# tracker4.net
KiCad netlist of a schematic drawn in EAGLE
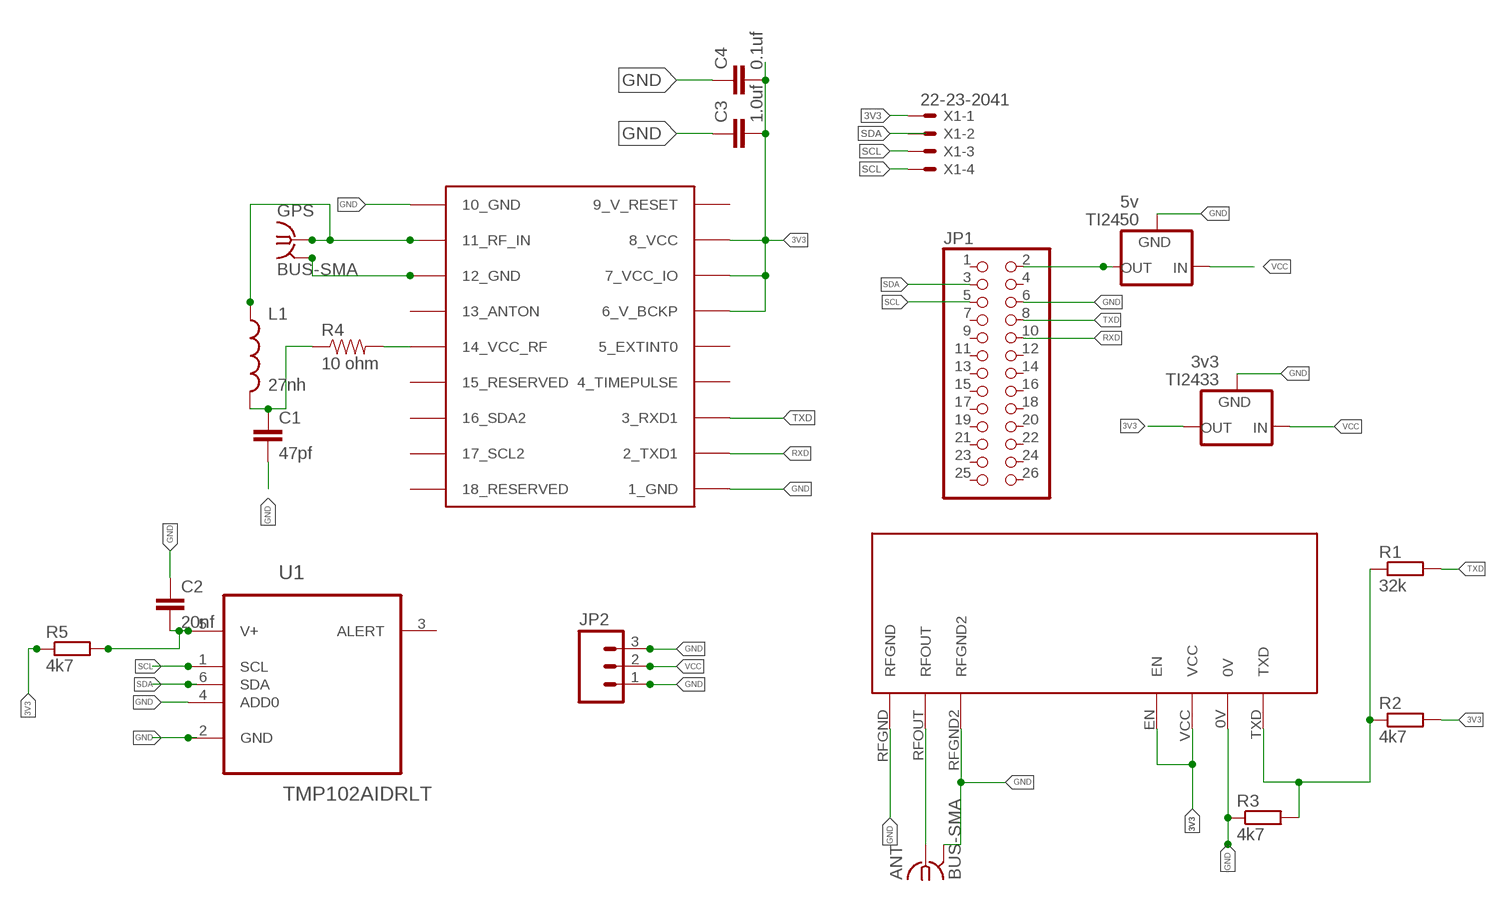
[diagram p0: schematic, sheet 1]

(export (version "E")
  (design (tool "Eeschema 10.0.6"))
  (components
    (comp (ref "ANT")
      (value "BUS-SMA")
      (footprint "eagle-import:BUS-SMA")
      (libsource (lib "eagle-import") (part "BUS-SMA"))
    )
    (comp (ref "C1")
      (value "47pf")
      (footprint "eagle-import:0603-CAP")
      (libsource (lib "eagle-import") (part "CAP0603-CAP"))
    )
    (comp (ref "C2")
      (value "20nf")
      (footprint "eagle-import:C0603")
      (libsource (lib "eagle-import") (part "C-EUC0603"))
    )
    (comp (ref "C3")
      (value "1.0uf")
      (footprint "eagle-import:C0603")
      (libsource (lib "eagle-import") (part "C-EUC0603"))
    )
    (comp (ref "C4")
      (value "0.1uf")
      (footprint "eagle-import:C0603")
      (libsource (lib "eagle-import") (part "C-EUC0603"))
    )
    (comp (ref "GPS")
      (value "BUS-SMA")
      (footprint "eagle-import:BUS-SMA")
      (libsource (lib "eagle-import") (part "BUS-SMA"))
    )
    (comp (ref "JP1")
      (value "PINHD-2X13")
      (footprint "eagle-import:2X13")
      (libsource (lib "eagle-import") (part "PINHD-2X13"))
    )
    (comp (ref "JP2")
      (value "M03PTH")
      (footprint "eagle-import:1X03")
      (libsource (lib "eagle-import") (part "M03PTH"))
    )
    (comp (ref "L1")
      (value "27nh")
      (footprint "eagle-import:0603")
      (libsource (lib "eagle-import") (part "INDUCTOR0603"))
    )
    (comp (ref "R1")
      (value "32k")
      (footprint "eagle-import:R0603")
      (libsource (lib "eagle-import") (part "R-EU_R0603"))
    )
    (comp (ref "R2")
      (value "4k7")
      (footprint "eagle-import:R0603")
      (libsource (lib "eagle-import") (part "R-EU_R0603"))
    )
    (comp (ref "R3")
      (value "4k7")
      (footprint "eagle-import:R0603")
      (libsource (lib "eagle-import") (part "R-EU_R0603"))
    )
    (comp (ref "R4")
      (value "10 ohm")
      (footprint "eagle-import:0603-RES")
      (libsource (lib "eagle-import") (part "RESISTOR0603"))
    )
    (comp (ref "R5")
      (value "4k7")
      (footprint "eagle-import:R0603")
      (libsource (lib "eagle-import") (part "R-EU_R0603"))
    )
    (comp (ref "TI2433")
      (value "3v3")
      (footprint "eagle-import:TO-220-ALT")
      (libsource (lib "eagle-import") (part "V_REG_78XX-TO-220"))
    )
    (comp (ref "TI2450")
      (value "5v")
      (footprint "eagle-import:TO-220-ALT")
      (libsource (lib "eagle-import") (part "V_REG_78XX-TO-220"))
    )
    (comp (ref "U$1")
      (value "NTX2")
      (footprint "eagle-import:NTX2")
      (libsource (lib "eagle-import") (part "NTX2"))
    )
    (comp (ref "U$2")
      (value "UBLOX_MAX")
      (footprint "eagle-import:UBLOX_MAX")
      (libsource (lib "eagle-import") (part "UBLOX_MAX"))
    )
    (comp (ref "U1")
      (value "TMP102AIDRLT")
      (footprint "eagle-import:SOT50P160X60-6N")
      (libsource (lib "eagle-import") (part "TMP102AIDRLT"))
    )
    (comp (ref "X1")
      (value "22-23-2041")
      (footprint "eagle-import:22-23-2041")
      (fields (field (name "MF") "MOLEX"))
      (libsource (lib "eagle-import") (part "22-23-2041"))
    )
  )
  (nets
    (net (code "1") (name "/9_V_RESET") (class "Default")
      (node (ref "U$2") (pin "9_V_RESET") (pinfunction "9_V_RESET_9_V_RESET") (pintype "power_in"))
    )
    (net (code "2") (name "3V3") (class "Default")
      (node (ref "C2") (pin "2") (pinfunction "2_2") (pintype "passive"))
      (node (ref "C3") (pin "2") (pinfunction "2_2") (pintype "passive"))
      (node (ref "C4") (pin "2") (pinfunction "2_2") (pintype "passive"))
      (node (ref "R2") (pin "2") (pinfunction "2_2") (pintype "passive"))
      (node (ref "R5") (pin "1") (pinfunction "1_1") (pintype "passive"))
      (node (ref "R5") (pin "2") (pinfunction "2_2") (pintype "passive"))
      (node (ref "TI2433") (pin "OUT") (pinfunction "OUT_OUT") (pintype "output"))
      (node (ref "U$1") (pin "EN") (pinfunction "EN_EN") (pintype "bidirectional"))
      (node (ref "U$1") (pin "VCC") (pinfunction "VCC_VCC") (pintype "bidirectional"))
      (node (ref "U$2") (pin "6_V_BCKP") (pinfunction "6_V_BCKP_6_V_BCKP") (pintype "bidirectional"))
      (node (ref "U$2") (pin "7_VCC_IO") (pinfunction "7_VCC_IO_7_VCC_IO") (pintype "power_in"))
      (node (ref "U$2") (pin "8_VCC") (pinfunction "8_VCC_8_VCC") (pintype "power_in"))
      (node (ref "U1") (pin "5") (pinfunction "V+_5") (pintype "power_in"))
      (node (ref "X1") (pin "1") (pinfunction "S_1") (pintype "passive"))
    )
    (net (code "3") (name "GND") (class "Default")
      (node (ref "ANT") (pin "2") (pinfunction "GND_2") (pintype "power_in"))
      (node (ref "ANT") (pin "3") (pinfunction "GND_3") (pintype "power_in"))
      (node (ref "ANT") (pin "4") (pinfunction "GND_4") (pintype "power_in"))
      (node (ref "ANT") (pin "5") (pinfunction "GND_5") (pintype "power_in"))
      (node (ref "C1") (pin "2") (pinfunction "2_2") (pintype "passive"))
      (node (ref "C2") (pin "1") (pinfunction "1_1") (pintype "passive"))
      (node (ref "C3") (pin "1") (pinfunction "1_1") (pintype "passive"))
      (node (ref "C4") (pin "1") (pinfunction "1_1") (pintype "passive"))
      (node (ref "GPS") (pin "2") (pinfunction "GND_2") (pintype "power_in"))
      (node (ref "GPS") (pin "3") (pinfunction "GND_3") (pintype "power_in"))
      (node (ref "GPS") (pin "4") (pinfunction "GND_4") (pintype "power_in"))
      (node (ref "GPS") (pin "5") (pinfunction "GND_5") (pintype "power_in"))
      (node (ref "JP1") (pin "6") (pinfunction "6_6") (pintype "passive"))
      (node (ref "JP2") (pin "1") (pinfunction "1_1") (pintype "passive"))
      (node (ref "JP2") (pin "3") (pinfunction "3_3") (pintype "passive"))
      (node (ref "R3") (pin "1") (pinfunction "1_1") (pintype "passive"))
      (node (ref "TI2433") (pin "GND") (pinfunction "GND_GND") (pintype "input"))
      (node (ref "TI2450") (pin "GND") (pinfunction "GND_GND") (pintype "input"))
      (node (ref "U$1") (pin "0V") (pinfunction "0V_0V") (pintype "bidirectional"))
      (node (ref "U$1") (pin "RFGND") (pinfunction "RFGND_RFGND") (pintype "bidirectional"))
      (node (ref "U$1") (pin "RFGND2") (pinfunction "RFGND2_RFGND2") (pintype "bidirectional"))
      (node (ref "U$2") (pin "10_GND") (pinfunction "10_GND_10_GND") (pintype "power_in"))
      (node (ref "U$2") (pin "12_GND") (pinfunction "12_GND_12_GND") (pintype "power_in"))
      (node (ref "U$2") (pin "1_GND") (pinfunction "1_GND_1_GND") (pintype "power_in"))
      (node (ref "U1") (pin "2") (pinfunction "GND_2") (pintype "passive"))
      (node (ref "U1") (pin "4") (pinfunction "ADD0_4") (pintype "input"))
      (node (ref "X1") (pin "4") (pinfunction "S_4") (pintype "passive"))
    )
    (net (code "4") (name "Net-(ANT-Pad1)") (class "Default")
      (node (ref "ANT") (pin "1") (pinfunction "1_1") (pintype "passive"))
      (node (ref "U$1") (pin "RFOUT") (pinfunction "RFOUT_RFOUT") (pintype "bidirectional"))
    )
    (net (code "5") (name "Net-(C1-Pad1)") (class "Default")
      (node (ref "C1") (pin "1") (pinfunction "1_1") (pintype "passive"))
      (node (ref "L1") (pin "2") (pinfunction "2_2") (pintype "passive"))
      (node (ref "R4") (pin "1") (pinfunction "1_1") (pintype "passive"))
    )
    (net (code "6") (name "Net-(GPS-Pad1)") (class "Default")
      (node (ref "GPS") (pin "1") (pinfunction "1_1") (pintype "passive"))
      (node (ref "L1") (pin "1") (pinfunction "1_1") (pintype "passive"))
      (node (ref "U$2") (pin "11_RF_IN") (pinfunction "11_RF_IN_11_RF_IN") (pintype "bidirectional"))
    )
    (net (code "7") (name "Net-(JP1-Pad2)") (class "Default")
      (node (ref "JP1") (pin "2") (pinfunction "2_2") (pintype "passive"))
      (node (ref "TI2450") (pin "OUT") (pinfunction "OUT_OUT") (pintype "output"))
    )
    (net (code "8") (name "Net-(R1-Pad1)") (class "Default")
      (node (ref "R1") (pin "1") (pinfunction "1_1") (pintype "passive"))
      (node (ref "R2") (pin "1") (pinfunction "1_1") (pintype "passive"))
      (node (ref "R3") (pin "2") (pinfunction "2_2") (pintype "passive"))
      (node (ref "U$1") (pin "TXD") (pinfunction "TXD_TXD") (pintype "bidirectional"))
    )
    (net (code "9") (name "Net-(R4-Pad2)") (class "Default")
      (node (ref "R4") (pin "2") (pinfunction "2_2") (pintype "passive"))
      (node (ref "U$2") (pin "14_VCC_RF") (pinfunction "14_VCC_RF_14_VCC_RF") (pintype "bidirectional"))
    )
    (net (code "10") (name "RXD") (class "Default")
      (node (ref "JP1") (pin "10") (pinfunction "10_10") (pintype "passive"))
      (node (ref "U$2") (pin "2_TXD1") (pinfunction "2_TXD1_2_TXD1") (pintype "bidirectional"))
    )
    (net (code "11") (name "SCL") (class "Default")
      (node (ref "JP1") (pin "5") (pinfunction "5_5") (pintype "passive"))
      (node (ref "U1") (pin "1") (pinfunction "SCL_1") (pintype "bidirectional"))
      (node (ref "X1") (pin "3") (pinfunction "S_3") (pintype "passive"))
    )
    (net (code "12") (name "SDA") (class "Default")
      (node (ref "JP1") (pin "3") (pinfunction "3_3") (pintype "passive"))
      (node (ref "U1") (pin "6") (pinfunction "SDA_6") (pintype "bidirectional"))
      (node (ref "X1") (pin "2") (pinfunction "S_2") (pintype "passive"))
    )
    (net (code "13") (name "TXD") (class "Default")
      (node (ref "JP1") (pin "8") (pinfunction "8_8") (pintype "passive"))
      (node (ref "R1") (pin "2") (pinfunction "2_2") (pintype "passive"))
      (node (ref "U$2") (pin "3_RXD1") (pinfunction "3_RXD1_3_RXD1") (pintype "bidirectional"))
    )
    (net (code "14") (name "VCC") (class "Default")
      (node (ref "JP2") (pin "2") (pinfunction "2_2") (pintype "passive"))
      (node (ref "TI2433") (pin "IN") (pinfunction "IN_IN") (pintype "input"))
      (node (ref "TI2450") (pin "IN") (pinfunction "IN_IN") (pintype "input"))
    )
    (net (code "15") (name "unconnected-(JP1-Pad1)") (class "Default")
      (node (ref "JP1") (pin "1") (pinfunction "1_1") (pintype "passive"))
    )
    (net (code "16") (name "unconnected-(JP1-Pad4)") (class "Default")
      (node (ref "JP1") (pin "4") (pinfunction "4_4") (pintype "passive"))
    )
    (net (code "17") (name "unconnected-(JP1-Pad7)") (class "Default")
      (node (ref "JP1") (pin "7") (pinfunction "7_7") (pintype "passive"))
    )
    (net (code "18") (name "unconnected-(JP1-Pad9)") (class "Default")
      (node (ref "JP1") (pin "9") (pinfunction "9_9") (pintype "passive"))
    )
    (net (code "19") (name "unconnected-(JP1-Pad11)") (class "Default")
      (node (ref "JP1") (pin "11") (pinfunction "11_11") (pintype "passive"))
    )
    (net (code "20") (name "unconnected-(JP1-Pad12)") (class "Default")
      (node (ref "JP1") (pin "12") (pinfunction "12_12") (pintype "passive"))
    )
    (net (code "21") (name "unconnected-(JP1-Pad13)") (class "Default")
      (node (ref "JP1") (pin "13") (pinfunction "13_13") (pintype "passive"))
    )
    (net (code "22") (name "unconnected-(JP1-Pad14)") (class "Default")
      (node (ref "JP1") (pin "14") (pinfunction "14_14") (pintype "passive"))
    )
    (net (code "23") (name "unconnected-(JP1-Pad15)") (class "Default")
      (node (ref "JP1") (pin "15") (pinfunction "15_15") (pintype "passive"))
    )
    (net (code "24") (name "unconnected-(JP1-Pad16)") (class "Default")
      (node (ref "JP1") (pin "16") (pinfunction "16_16") (pintype "passive"))
    )
    (net (code "25") (name "unconnected-(JP1-Pad17)") (class "Default")
      (node (ref "JP1") (pin "17") (pinfunction "17_17") (pintype "passive"))
    )
    (net (code "26") (name "unconnected-(JP1-Pad18)") (class "Default")
      (node (ref "JP1") (pin "18") (pinfunction "18_18") (pintype "passive"))
    )
    (net (code "27") (name "unconnected-(JP1-Pad19)") (class "Default")
      (node (ref "JP1") (pin "19") (pinfunction "19_19") (pintype "passive"))
    )
    (net (code "28") (name "unconnected-(JP1-Pad20)") (class "Default")
      (node (ref "JP1") (pin "20") (pinfunction "20_20") (pintype "passive"))
    )
    (net (code "29") (name "unconnected-(JP1-Pad21)") (class "Default")
      (node (ref "JP1") (pin "21") (pinfunction "21_21") (pintype "passive"))
    )
    (net (code "30") (name "unconnected-(JP1-Pad22)") (class "Default")
      (node (ref "JP1") (pin "22") (pinfunction "22_22") (pintype "passive"))
    )
    (net (code "31") (name "unconnected-(JP1-Pad23)") (class "Default")
      (node (ref "JP1") (pin "23") (pinfunction "23_23") (pintype "passive"))
    )
    (net (code "32") (name "unconnected-(JP1-Pad24)") (class "Default")
      (node (ref "JP1") (pin "24") (pinfunction "24_24") (pintype "passive"))
    )
    (net (code "33") (name "unconnected-(JP1-Pad25)") (class "Default")
      (node (ref "JP1") (pin "25") (pinfunction "25_25") (pintype "passive"))
    )
    (net (code "34") (name "unconnected-(JP1-Pad26)") (class "Default")
      (node (ref "JP1") (pin "26") (pinfunction "26_26") (pintype "passive"))
    )
    (net (code "35") (name "unconnected-(U$2-Pad4_TIMEPULSE)") (class "Default")
      (node (ref "U$2") (pin "4_TIMEPULSE") (pinfunction "4_TIMEPULSE_4_TIMEPULSE") (pintype "bidirectional"))
    )
    (net (code "36") (name "unconnected-(U$2-Pad5_EXTINT0)") (class "Default")
      (node (ref "U$2") (pin "5_EXTINT0") (pinfunction "5_EXTINT0_5_EXTINT0") (pintype "bidirectional"))
    )
    (net (code "37") (name "unconnected-(U$2-Pad13_ANTON)") (class "Default")
      (node (ref "U$2") (pin "13_ANTON") (pinfunction "13_ANTON_13_ANTON") (pintype "bidirectional"))
    )
    (net (code "38") (name "unconnected-(U$2-Pad15_RESERVED)") (class "Default")
      (node (ref "U$2") (pin "15_RESERVED") (pinfunction "15_RESERVED_15_RESERVED") (pintype "bidirectional"))
    )
    (net (code "39") (name "unconnected-(U$2-Pad16_SDA2)") (class "Default")
      (node (ref "U$2") (pin "16_SDA2") (pinfunction "16_SDA2_16_SDA2") (pintype "bidirectional"))
    )
    (net (code "40") (name "unconnected-(U$2-Pad17_SCL2)") (class "Default")
      (node (ref "U$2") (pin "17_SCL2") (pinfunction "17_SCL2_17_SCL2") (pintype "bidirectional"))
    )
    (net (code "41") (name "unconnected-(U$2-Pad18_RESERVED)") (class "Default")
      (node (ref "U$2") (pin "18_RESERVED") (pinfunction "18_RESERVED_18_RESERVED") (pintype "bidirectional"))
    )
    (net (code "42") (name "unconnected-(U1-ALERT-Pad3)") (class "Default")
      (node (ref "U1") (pin "3") (pinfunction "ALERT_3") (pintype "output"))
    )
  )
)
